# OZ440-SE100-CAR003_sheet17.net
KiCad netlist of a schematic drawn in Altium Designer
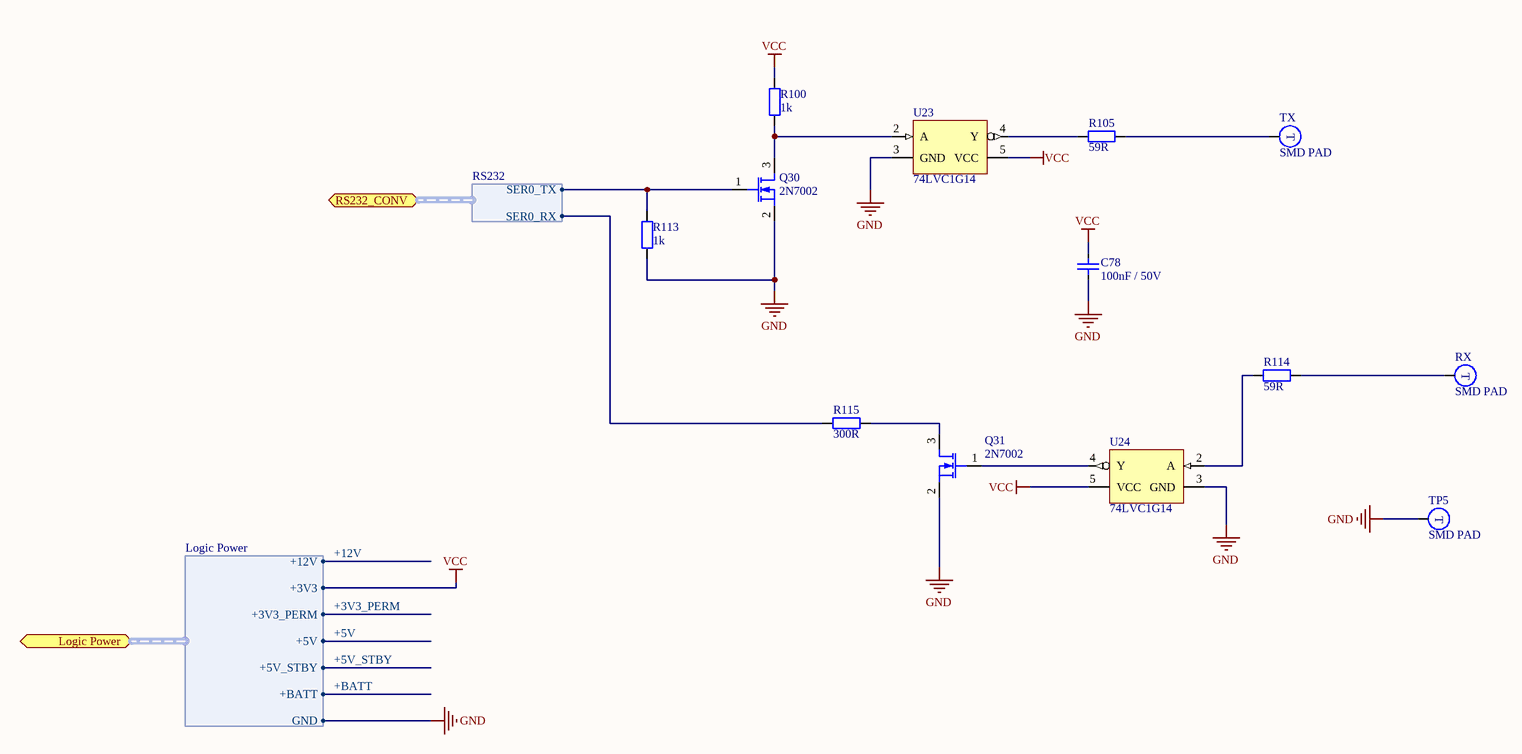
[diagram p0: OZ440-SE100-CAR003_sheet17.SchDoc]

(export (version "E")
  (design (tool "Eeschema 10.0.6"))
  (components
    (comp (ref "C78")
      (value "CAP-SMD")
      (footprint "C0805-STD")
      (description "0805 100nF / 50V  X7R ceramic capacitor")
      (fields
        (field (name "DISPLAYED REFERENCE") "100nF / 50V")
        (field (name "TOLERANCE") "+/- 10%")
        (field (name "MANUFACTURER") "vishay")
      )
      (libsource (lib "lib_NAIO") (part "CAP-SMD"))
    )
    (comp (ref "Q30")
      (value "2N7002-SMD3P")
      (footprint "SOT23-SPE-2N7002")
      (description "N-Channel Enhancement Mode Field Effect Transistor")
      (fields (field (name "DISPLAYED REFERENCE") "2N7002") (field (name "MANUFACTURER") "FAIRCHILD"))
      (libsource (lib "lib_NAIO") (part "2N7002-SMD3P"))
    )
    (comp (ref "Q31")
      (value "2N7002-SMD3P")
      (footprint "SOT23-SPE-2N7002")
      (description "N-Channel Enhancement Mode Field Effect Transistor")
      (fields (field (name "DISPLAYED REFERENCE") "2N7002") (field (name "MANUFACTURER") "FAIRCHILD"))
      (libsource (lib "lib_NAIO") (part "2N7002-SMD3P"))
    )
    (comp (ref "R100")
      (value "RES-SMD")
      (footprint "R0805-STD")
      (description "1k Ohm 0805 SMD resistor")
      (fields
        (field (name "DISPLAYED REFERENCE") "1k")
        (field (name "TOLERANCE") "1 %")
        (field (name "MANUFACTURER") "Vishay")
      )
      (libsource (lib "lib_NAIO") (part "RES-SMD"))
    )
    (comp (ref "R105")
      (value "RES-SMD")
      (footprint "R0805-STD")
      (description "59 Ohm 0805 SMD resistor")
      (fields
        (field (name "DISPLAYED REFERENCE") "59R")
        (field (name "TOLERANCE") "1 %")
        (field (name "MANUFACTURER") "Vishay")
      )
      (libsource (lib "") (part "RES-SMD_1"))
    )
    (comp (ref "R113")
      (value "RES-SMD")
      (footprint "R0805-STD")
      (description "1k Ohm 0805 SMD resistor")
      (fields
        (field (name "DISPLAYED REFERENCE") "1k")
        (field (name "TOLERANCE") "1 %")
        (field (name "MANUFACTURER") "Vishay")
      )
      (libsource (lib "lib_NAIO") (part "RES-SMD"))
    )
    (comp (ref "R114")
      (value "RES-SMD")
      (footprint "R0805-STD")
      (description "59 Ohm 0805 SMD resistor")
      (fields
        (field (name "DISPLAYED REFERENCE") "59R")
        (field (name "TOLERANCE") "1 %")
        (field (name "MANUFACTURER") "Vishay")
      )
      (libsource (lib "") (part "RES-SMD_1"))
    )
    (comp (ref "R115")
      (value "RES-SMD")
      (footprint "R0805-STD")
      (description "300 ohm 0805 SMD resistor")
      (fields
        (field (name "DISPLAYED REFERENCE") "300R")
        (field (name "TOLERANCE") "1%")
        (field (name "MANUFACTURER") "Vishay")
      )
      (libsource (lib "") (part "RES-SMD_2"))
    )
    (comp (ref "RX")
      (value "TP-STD-TEST_POINT")
      (footprint "MEC-STD-SMD_PAD_2mm")
      (description "SMD Pad for wire soldering")
      (fields (field (name "DISPLAYED REFERENCE") "SMD PAD"))
      (libsource (lib "lib_NAIO") (part "TP-STD-TEST_POINT"))
    )
    (comp (ref "TP5")
      (value "TP-STD-TEST_POINT")
      (footprint "MEC-STD-SMD_PAD_2mm")
      (description "SMD Pad for wire soldering")
      (fields (field (name "DISPLAYED REFERENCE") "SMD PAD"))
      (libsource (lib "lib_NAIO") (part "TP-STD-TEST_POINT"))
    )
    (comp (ref "TX")
      (value "TP-STD-TEST_POINT")
      (footprint "MEC-STD-SMD_PAD_2mm")
      (description "SMD Pad for wire soldering")
      (fields (field (name "DISPLAYED REFERENCE") "SMD PAD"))
      (libsource (lib "lib_NAIO") (part "TP-STD-TEST_POINT"))
    )
    (comp (ref "U23")
      (value "74xxx1G14GW-SOT353-1")
      (footprint "SOT353-1_5pin-STD")
      (description "smith trigger inverter")
      (fields (field (name "DISPLAYED REFERENCE") "74LVC1G14") (field (name "MANUFACTURER") "NXP"))
      (libsource (lib "lib_NAIO") (part "74xxx1G14GW-SOT353-1"))
    )
    (comp (ref "U24")
      (value "74xxx1G14GW-SOT353-1")
      (footprint "SOT353-1_5pin-STD")
      (description "smith trigger inverter")
      (fields (field (name "DISPLAYED REFERENCE") "74LVC1G14") (field (name "MANUFACTURER") "NXP"))
      (libsource (lib "") (part "74xxx1G14GW-SOT353-1_1"))
    )
  )
  (nets
    (net (code "9") (name "/SER0_RX") (class "Default")
      (node (ref "R115") (pin "2") (pinfunction "2_2") (pintype "passive"))
    )
    (net (code "10") (name "/SER0_TX") (class "Default")
      (node (ref "Q30") (pin "1") (pinfunction "G_1") (pintype "passive"))
      (node (ref "R113") (pin "2") (pinfunction "2_2") (pintype "passive"))
    )
    (net (code "13") (name "GND") (class "Default")
      (node (ref "C78") (pin "1") (pinfunction "1_1") (pintype "passive"))
      (node (ref "Q30") (pin "2") (pinfunction "S_2") (pintype "passive"))
      (node (ref "Q31") (pin "2") (pinfunction "S_2") (pintype "passive"))
      (node (ref "R113") (pin "1") (pinfunction "1_1") (pintype "passive"))
      (node (ref "TP5") (pin "1") (pinfunction "T_1") (pintype "passive"))
      (node (ref "U23") (pin "3") (pinfunction "GND_3") (pintype "power_in"))
      (node (ref "U24") (pin "3") (pinfunction "GND_3") (pintype "power_in"))
    )
    (net (code "14") (name "Net-(Q30-D)") (class "Default")
      (node (ref "Q30") (pin "3") (pinfunction "D_3") (pintype "passive"))
      (node (ref "R100") (pin "1") (pinfunction "1_1") (pintype "passive"))
      (node (ref "U23") (pin "2") (pinfunction "A_2") (pintype "input"))
    )
    (net (code "15") (name "Net-(Q31-D)") (class "Default")
      (node (ref "Q31") (pin "3") (pinfunction "D_3") (pintype "passive"))
      (node (ref "R115") (pin "1") (pinfunction "1_1") (pintype "passive"))
    )
    (net (code "16") (name "Net-(Q31-G)") (class "Default")
      (node (ref "Q31") (pin "1") (pinfunction "G_1") (pintype "passive"))
      (node (ref "U24") (pin "4") (pinfunction "Y_4") (pintype "output"))
    )
    (net (code "17") (name "Net-(RX-T)") (class "Default")
      (node (ref "R114") (pin "2") (pinfunction "2_2") (pintype "passive"))
      (node (ref "RX") (pin "1") (pinfunction "T_1") (pintype "passive"))
    )
    (net (code "18") (name "Net-(TX-T)") (class "Default")
      (node (ref "R105") (pin "2") (pinfunction "2_2") (pintype "passive"))
      (node (ref "TX") (pin "1") (pinfunction "T_1") (pintype "passive"))
    )
    (net (code "19") (name "Net-(U23-Y)") (class "Default")
      (node (ref "R105") (pin "1") (pinfunction "1_1") (pintype "passive"))
      (node (ref "U23") (pin "4") (pinfunction "Y_4") (pintype "output"))
    )
    (net (code "20") (name "Net-(U24-A)") (class "Default")
      (node (ref "R114") (pin "1") (pinfunction "1_1") (pintype "passive"))
      (node (ref "U24") (pin "2") (pinfunction "A_2") (pintype "input"))
    )
    (net (code "21") (name "VCC") (class "Default")
      (node (ref "C78") (pin "2") (pinfunction "2_2") (pintype "passive"))
      (node (ref "R100") (pin "2") (pinfunction "2_2") (pintype "passive"))
      (node (ref "U23") (pin "5") (pinfunction "VCC_5") (pintype "power_in"))
      (node (ref "U24") (pin "5") (pinfunction "VCC_5") (pintype "power_in"))
    )
  )
)
